# board.net
KiCad netlist of a schematic drawn in EAGLE
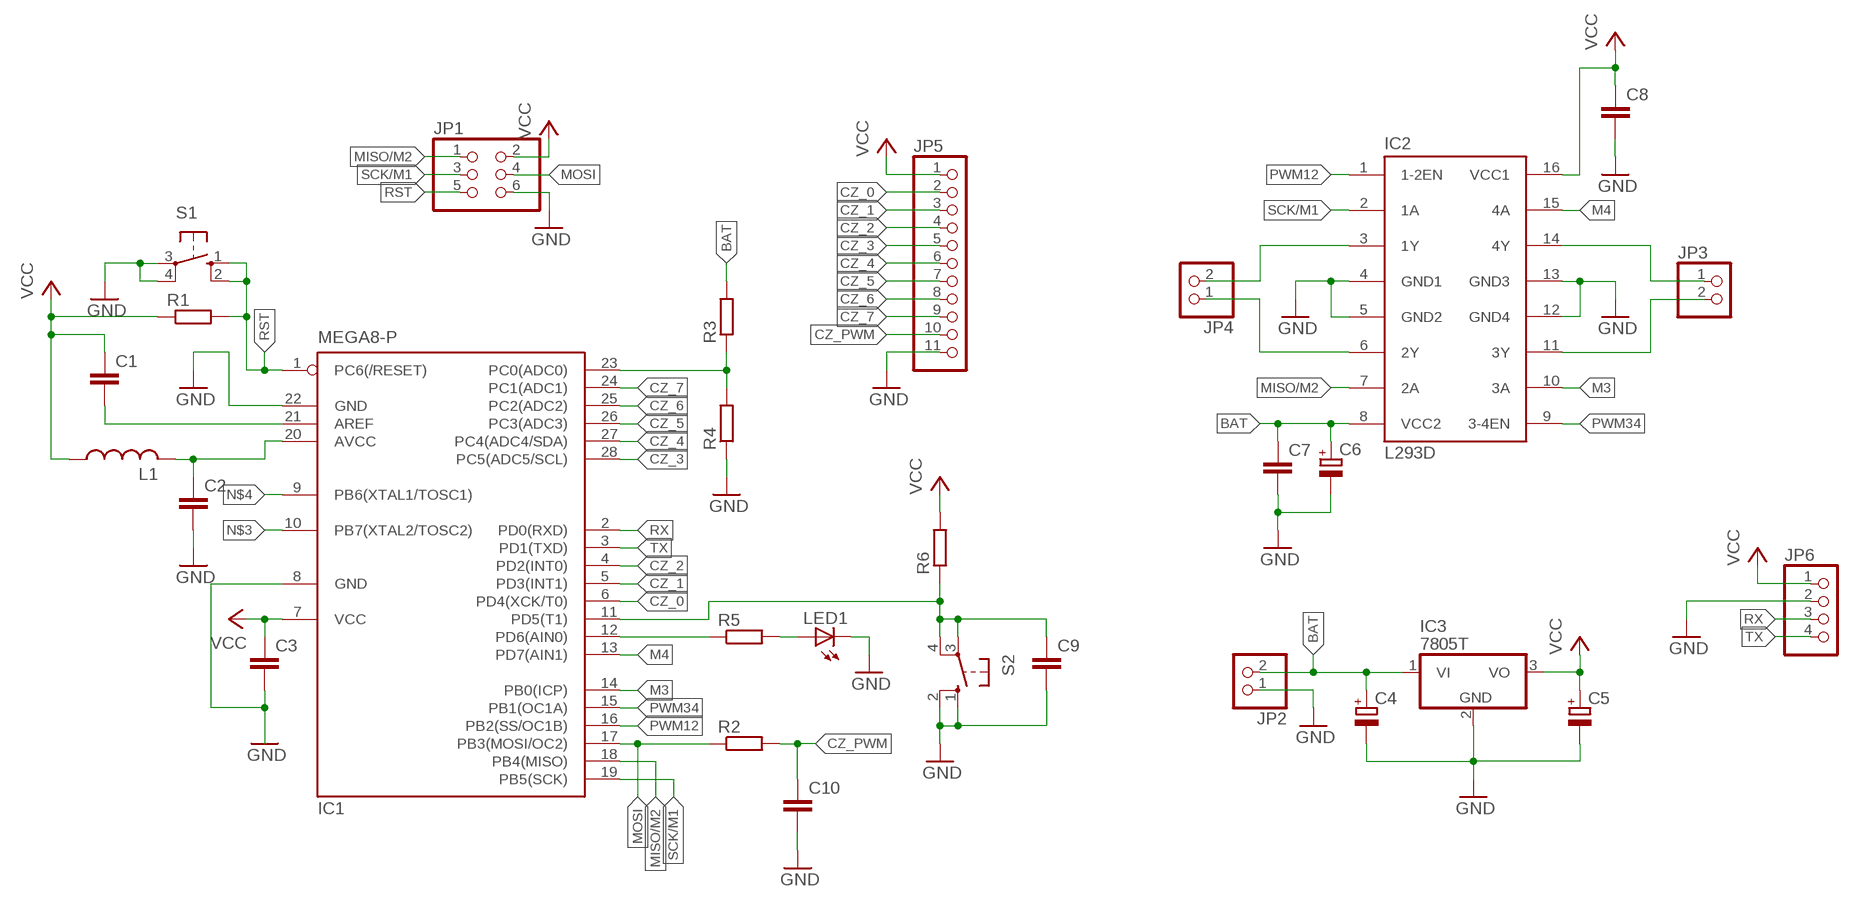
[diagram p0: schematic, sheet 1]

(export (version "E")
  (design (tool "Eeschema 10.0.6"))
  (components
    (comp (ref "C1")
      (value "C-EU025-025X050")
      (footprint "eagle-import:C025-025X050")
      (libsource (lib "eagle-import") (part "C-EU025-025X050"))
    )
    (comp (ref "C2")
      (value "C-EU025-025X050")
      (footprint "eagle-import:C025-025X050")
      (libsource (lib "eagle-import") (part "C-EU025-025X050"))
    )
    (comp (ref "C3")
      (value "C-EU025-025X050")
      (footprint "eagle-import:C025-025X050")
      (libsource (lib "eagle-import") (part "C-EU025-025X050"))
    )
    (comp (ref "C4")
      (value "CPOL-EUE2-5")
      (footprint "eagle-import:E2-5")
      (libsource (lib "eagle-import") (part "CPOL-EUE2-5"))
    )
    (comp (ref "C5")
      (value "CPOL-EUE2-5")
      (footprint "eagle-import:E2-5")
      (libsource (lib "eagle-import") (part "CPOL-EUE2-5"))
    )
    (comp (ref "C6")
      (value "CPOL-EUE2-5")
      (footprint "eagle-import:E2-5")
      (libsource (lib "eagle-import") (part "CPOL-EUE2-5"))
    )
    (comp (ref "C7")
      (value "C-EU025-025X050")
      (footprint "eagle-import:C025-025X050")
      (libsource (lib "eagle-import") (part "C-EU025-025X050"))
    )
    (comp (ref "C8")
      (value "C-EU025-025X050")
      (footprint "eagle-import:C025-025X050")
      (libsource (lib "eagle-import") (part "C-EU025-025X050"))
    )
    (comp (ref "C9")
      (value "C-EU025-025X050")
      (footprint "eagle-import:C025-025X050")
      (libsource (lib "eagle-import") (part "C-EU025-025X050"))
    )
    (comp (ref "C10")
      (value "C-EU050-035X075")
      (footprint "eagle-import:C050-035X075")
      (libsource (lib "eagle-import") (part "C-EU050-035X075"))
    )
    (comp (ref "IC1")
      (value "MEGA8-P")
      (footprint "eagle-import:DIL28-3")
      (libsource (lib "eagle-import") (part "MEGA8-P"))
    )
    (comp (ref "IC2")
      (value "L293D")
      (footprint "eagle-import:DIL16")
      (libsource (lib "eagle-import") (part "L293D"))
    )
    (comp (ref "IC3")
      (value "7805T")
      (footprint "eagle-import:TO220H")
      (libsource (lib "eagle-import") (part "78T05"))
    )
    (comp (ref "JP1")
      (value "PINHD-2X3")
      (footprint "eagle-import:2X03")
      (libsource (lib "eagle-import") (part "PINHD-2X3"))
    )
    (comp (ref "JP2")
      (value "PINHD-1X2")
      (footprint "eagle-import:1X02")
      (libsource (lib "eagle-import") (part "PINHD-1X2"))
    )
    (comp (ref "JP3")
      (value "PINHD-1X2")
      (footprint "eagle-import:1X02")
      (libsource (lib "eagle-import") (part "PINHD-1X2"))
    )
    (comp (ref "JP4")
      (value "PINHD-1X2")
      (footprint "eagle-import:1X02")
      (libsource (lib "eagle-import") (part "PINHD-1X2"))
    )
    (comp (ref "JP5")
      (value "PINHD-1X11")
      (footprint "eagle-import:1X11")
      (libsource (lib "eagle-import") (part "PINHD-1X11"))
    )
    (comp (ref "JP6")
      (value "PINHD-1X4")
      (footprint "eagle-import:1X04")
      (libsource (lib "eagle-import") (part "PINHD-1X4"))
    )
    (comp (ref "L1")
      (value "L-US0204/7")
      (footprint "eagle-import:0204_7")
      (libsource (lib "eagle-import") (part "L-US0204/7"))
    )
    (comp (ref "LED1")
      (value "LED5MM")
      (footprint "eagle-import:LED5MM")
      (libsource (lib "eagle-import") (part "LED5MM"))
    )
    (comp (ref "R1")
      (value "R-EU_0207/7")
      (footprint "eagle-import:0207_7")
      (libsource (lib "eagle-import") (part "R-EU_0207/7"))
    )
    (comp (ref "R2")
      (value "R-EU_0207/7")
      (footprint "eagle-import:0207_7")
      (libsource (lib "eagle-import") (part "R-EU_0207/7"))
    )
    (comp (ref "R3")
      (value "R-EU_0207/7")
      (footprint "eagle-import:0207_7")
      (libsource (lib "eagle-import") (part "R-EU_0207/7"))
    )
    (comp (ref "R4")
      (value "R-EU_0207/7")
      (footprint "eagle-import:0207_7")
      (libsource (lib "eagle-import") (part "R-EU_0207/7"))
    )
    (comp (ref "R5")
      (value "R-EU_0207/7")
      (footprint "eagle-import:0207_7")
      (libsource (lib "eagle-import") (part "R-EU_0207/7"))
    )
    (comp (ref "R6")
      (value "R-EU_0207/7")
      (footprint "eagle-import:0207_7")
      (libsource (lib "eagle-import") (part "R-EU_0207/7"))
    )
    (comp (ref "S1")
      (value "10-XX")
      (footprint "eagle-import:B3F-10XX")
      (fields (field (name "MPN") "B3F-1000"))
      (libsource (lib "eagle-import") (part "10-XX"))
    )
    (comp (ref "S2")
      (value "10-XX")
      (footprint "eagle-import:B3F-10XX")
      (fields (field (name "MPN") "B3F-1000"))
      (libsource (lib "eagle-import") (part "10-XX"))
    )
  )
  (nets
    (net (code "1") (name "BAT") (class "Default")
      (node (ref "C4") (pin "+") (pinfunction "+_+") (pintype "passive"))
      (node (ref "C6") (pin "+") (pinfunction "+_+") (pintype "passive"))
      (node (ref "C7") (pin "1") (pinfunction "1_1") (pintype "passive"))
      (node (ref "IC2") (pin "8") (pinfunction "VCC2_8") (pintype "power_in"))
      (node (ref "IC3") (pin "1") (pinfunction "VI_1") (pintype "input"))
      (node (ref "JP2") (pin "2") (pinfunction "2_2") (pintype "passive"))
      (node (ref "R3") (pin "2") (pinfunction "2_2") (pintype "passive"))
    )
    (net (code "2") (name "CZ_0") (class "Default")
      (node (ref "IC1") (pin "6") (pinfunction "PD4(XCK/T0)_6") (pintype "bidirectional"))
      (node (ref "JP5") (pin "2") (pinfunction "2_2") (pintype "passive"))
    )
    (net (code "3") (name "CZ_1") (class "Default")
      (node (ref "IC1") (pin "5") (pinfunction "PD3(INT1)_5") (pintype "bidirectional"))
      (node (ref "JP5") (pin "3") (pinfunction "3_3") (pintype "passive"))
    )
    (net (code "4") (name "CZ_2") (class "Default")
      (node (ref "IC1") (pin "4") (pinfunction "PD2(INT0)_4") (pintype "bidirectional"))
      (node (ref "JP5") (pin "4") (pinfunction "4_4") (pintype "passive"))
    )
    (net (code "5") (name "CZ_3") (class "Default")
      (node (ref "IC1") (pin "28") (pinfunction "PC5(ADC5/SCL)_28") (pintype "bidirectional"))
      (node (ref "JP5") (pin "5") (pinfunction "5_5") (pintype "passive"))
    )
    (net (code "6") (name "CZ_4") (class "Default")
      (node (ref "IC1") (pin "27") (pinfunction "PC4(ADC4/SDA)_27") (pintype "bidirectional"))
      (node (ref "JP5") (pin "6") (pinfunction "6_6") (pintype "passive"))
    )
    (net (code "7") (name "CZ_5") (class "Default")
      (node (ref "IC1") (pin "26") (pinfunction "PC3(ADC3)_26") (pintype "bidirectional"))
      (node (ref "JP5") (pin "7") (pinfunction "7_7") (pintype "passive"))
    )
    (net (code "8") (name "CZ_6") (class "Default")
      (node (ref "IC1") (pin "25") (pinfunction "PC2(ADC2)_25") (pintype "bidirectional"))
      (node (ref "JP5") (pin "8") (pinfunction "8_8") (pintype "passive"))
    )
    (net (code "9") (name "CZ_7") (class "Default")
      (node (ref "IC1") (pin "24") (pinfunction "PC1(ADC1)_24") (pintype "bidirectional"))
      (node (ref "JP5") (pin "9") (pinfunction "9_9") (pintype "passive"))
    )
    (net (code "10") (name "CZ_PWM") (class "Default")
      (node (ref "C10") (pin "1") (pinfunction "1_1") (pintype "passive"))
      (node (ref "JP5") (pin "10") (pinfunction "10_10") (pintype "passive"))
      (node (ref "R2") (pin "2") (pinfunction "2_2") (pintype "passive"))
    )
    (net (code "11") (name "GND") (class "Default")
      (node (ref "C10") (pin "2") (pinfunction "2_2") (pintype "passive"))
      (node (ref "C2") (pin "2") (pinfunction "2_2") (pintype "passive"))
      (node (ref "C3") (pin "2") (pinfunction "2_2") (pintype "passive"))
      (node (ref "C4") (pin "-") (pinfunction "-_-") (pintype "passive"))
      (node (ref "C5") (pin "-") (pinfunction "-_-") (pintype "passive"))
      (node (ref "C6") (pin "-") (pinfunction "-_-") (pintype "passive"))
      (node (ref "C7") (pin "2") (pinfunction "2_2") (pintype "passive"))
      (node (ref "C8") (pin "2") (pinfunction "2_2") (pintype "passive"))
      (node (ref "C9") (pin "2") (pinfunction "2_2") (pintype "passive"))
      (node (ref "IC1") (pin "22") (pinfunction "GND_22") (pintype "power_in"))
      (node (ref "IC1") (pin "8") (pinfunction "GND_8") (pintype "power_in"))
      (node (ref "IC2") (pin "12") (pinfunction "GND4_12") (pintype "power_in"))
      (node (ref "IC2") (pin "13") (pinfunction "GND3_13") (pintype "power_in"))
      (node (ref "IC2") (pin "4") (pinfunction "GND1_4") (pintype "power_in"))
      (node (ref "IC2") (pin "5") (pinfunction "GND2_5") (pintype "power_in"))
      (node (ref "IC3") (pin "2") (pinfunction "GND_2") (pintype "passive"))
      (node (ref "JP1") (pin "6") (pinfunction "6_6") (pintype "passive"))
      (node (ref "JP2") (pin "1") (pinfunction "1_1") (pintype "passive"))
      (node (ref "JP5") (pin "11") (pinfunction "11_11") (pintype "passive"))
      (node (ref "JP6") (pin "2") (pinfunction "2_2") (pintype "passive"))
      (node (ref "LED1") (pin "K") (pinfunction "C_K") (pintype "passive"))
      (node (ref "R4") (pin "1") (pinfunction "1_1") (pintype "passive"))
      (node (ref "S1") (pin "3") (pinfunction "P_3") (pintype "passive"))
      (node (ref "S1") (pin "4") (pinfunction "P1_4") (pintype "passive"))
      (node (ref "S2") (pin "1") (pinfunction "S_1") (pintype "passive"))
      (node (ref "S2") (pin "2") (pinfunction "S1_2") (pintype "passive"))
    )
    (net (code "12") (name "M3") (class "Default")
      (node (ref "IC1") (pin "14") (pinfunction "PB0(ICP)_14") (pintype "bidirectional"))
      (node (ref "IC2") (pin "10") (pinfunction "3A_10") (pintype "input"))
    )
    (net (code "13") (name "M4") (class "Default")
      (node (ref "IC1") (pin "13") (pinfunction "PD7(AIN1)_13") (pintype "bidirectional"))
      (node (ref "IC2") (pin "15") (pinfunction "4A_15") (pintype "input"))
    )
    (net (code "14") (name "MISO{slash}M2") (class "Default")
      (node (ref "IC1") (pin "18") (pinfunction "PB4(MISO)_18") (pintype "bidirectional"))
      (node (ref "IC2") (pin "7") (pinfunction "2A_7") (pintype "input"))
      (node (ref "JP1") (pin "1") (pinfunction "1_1") (pintype "passive"))
    )
    (net (code "15") (name "MOSI") (class "Default")
      (node (ref "IC1") (pin "17") (pinfunction "PB3(MOSI/OC2)_17") (pintype "bidirectional"))
      (node (ref "JP1") (pin "4") (pinfunction "4_4") (pintype "passive"))
      (node (ref "R2") (pin "1") (pinfunction "1_1") (pintype "passive"))
    )
    (net (code "16") (name "N$3") (class "Default")
      (node (ref "IC1") (pin "10") (pinfunction "PB7(XTAL2/TOSC2)_10") (pintype "bidirectional"))
    )
    (net (code "17") (name "N$4") (class "Default")
      (node (ref "IC1") (pin "9") (pinfunction "PB6(XTAL1/TOSC1)_9") (pintype "bidirectional"))
    )
    (net (code "18") (name "Net-(IC1-AREF)") (class "Default")
      (node (ref "C1") (pin "2") (pinfunction "2_2") (pintype "passive"))
      (node (ref "IC1") (pin "21") (pinfunction "AREF_21") (pintype "passive"))
    )
    (net (code "19") (name "Net-(IC1-AVCC)") (class "Default")
      (node (ref "C2") (pin "1") (pinfunction "1_1") (pintype "passive"))
      (node (ref "IC1") (pin "20") (pinfunction "AVCC_20") (pintype "power_in"))
      (node (ref "L1") (pin "2") (pinfunction "2_2") (pintype "passive"))
    )
    (net (code "20") (name "Net-(IC1-PC0(ADC0))") (class "Default")
      (node (ref "IC1") (pin "23") (pinfunction "PC0(ADC0)_23") (pintype "bidirectional"))
      (node (ref "R3") (pin "1") (pinfunction "1_1") (pintype "passive"))
      (node (ref "R4") (pin "2") (pinfunction "2_2") (pintype "passive"))
    )
    (net (code "21") (name "Net-(IC1-PD5(T1))") (class "Default")
      (node (ref "C9") (pin "1") (pinfunction "1_1") (pintype "passive"))
      (node (ref "IC1") (pin "11") (pinfunction "PD5(T1)_11") (pintype "bidirectional"))
      (node (ref "R6") (pin "1") (pinfunction "1_1") (pintype "passive"))
      (node (ref "S2") (pin "3") (pinfunction "P_3") (pintype "passive"))
      (node (ref "S2") (pin "4") (pinfunction "P1_4") (pintype "passive"))
    )
    (net (code "22") (name "Net-(IC1-PD6(AIN0))") (class "Default")
      (node (ref "IC1") (pin "12") (pinfunction "PD6(AIN0)_12") (pintype "bidirectional"))
      (node (ref "R5") (pin "1") (pinfunction "1_1") (pintype "passive"))
    )
    (net (code "23") (name "Net-(IC2-1Y)") (class "Default")
      (node (ref "IC2") (pin "3") (pinfunction "1Y_3") (pintype "output"))
      (node (ref "JP4") (pin "2") (pinfunction "2_2") (pintype "passive"))
    )
    (net (code "24") (name "Net-(IC2-2Y)") (class "Default")
      (node (ref "IC2") (pin "6") (pinfunction "2Y_6") (pintype "output"))
      (node (ref "JP4") (pin "1") (pinfunction "1_1") (pintype "passive"))
    )
    (net (code "25") (name "Net-(IC2-3Y)") (class "Default")
      (node (ref "IC2") (pin "11") (pinfunction "3Y_11") (pintype "output"))
      (node (ref "JP3") (pin "2") (pinfunction "2_2") (pintype "passive"))
    )
    (net (code "26") (name "Net-(IC2-4Y)") (class "Default")
      (node (ref "IC2") (pin "14") (pinfunction "4Y_14") (pintype "output"))
      (node (ref "JP3") (pin "1") (pinfunction "1_1") (pintype "passive"))
    )
    (net (code "27") (name "Net-(LED1-PadA)") (class "Default")
      (node (ref "LED1") (pin "A") (pinfunction "A_A") (pintype "passive"))
      (node (ref "R5") (pin "2") (pinfunction "2_2") (pintype "passive"))
    )
    (net (code "28") (name "PWM12") (class "Default")
      (node (ref "IC1") (pin "16") (pinfunction "PB2(SS/OC1B)_16") (pintype "bidirectional"))
      (node (ref "IC2") (pin "1") (pinfunction "1-2EN_1") (pintype "input"))
    )
    (net (code "29") (name "PWM34") (class "Default")
      (node (ref "IC1") (pin "15") (pinfunction "PB1(OC1A)_15") (pintype "bidirectional"))
      (node (ref "IC2") (pin "9") (pinfunction "3-4EN_9") (pintype "input"))
    )
    (net (code "30") (name "RST") (class "Default")
      (node (ref "IC1") (pin "1") (pinfunction "PC6(/RESET)_1") (pintype "bidirectional"))
      (node (ref "JP1") (pin "5") (pinfunction "5_5") (pintype "passive"))
      (node (ref "R1") (pin "2") (pinfunction "2_2") (pintype "passive"))
      (node (ref "S1") (pin "1") (pinfunction "S_1") (pintype "passive"))
      (node (ref "S1") (pin "2") (pinfunction "S1_2") (pintype "passive"))
    )
    (net (code "31") (name "RX") (class "Default")
      (node (ref "IC1") (pin "2") (pinfunction "PD0(RXD)_2") (pintype "bidirectional"))
      (node (ref "JP6") (pin "3") (pinfunction "3_3") (pintype "passive"))
    )
    (net (code "32") (name "SCK{slash}M1") (class "Default")
      (node (ref "IC1") (pin "19") (pinfunction "PB5(SCK)_19") (pintype "bidirectional"))
      (node (ref "IC2") (pin "2") (pinfunction "1A_2") (pintype "input"))
      (node (ref "JP1") (pin "3") (pinfunction "3_3") (pintype "passive"))
    )
    (net (code "33") (name "TX") (class "Default")
      (node (ref "IC1") (pin "3") (pinfunction "PD1(TXD)_3") (pintype "bidirectional"))
      (node (ref "JP6") (pin "4") (pinfunction "4_4") (pintype "passive"))
    )
    (net (code "34") (name "VCC") (class "Default")
      (node (ref "C1") (pin "1") (pinfunction "1_1") (pintype "passive"))
      (node (ref "C3") (pin "1") (pinfunction "1_1") (pintype "passive"))
      (node (ref "C5") (pin "+") (pinfunction "+_+") (pintype "passive"))
      (node (ref "C8") (pin "1") (pinfunction "1_1") (pintype "passive"))
      (node (ref "IC1") (pin "7") (pinfunction "VCC_7") (pintype "power_in"))
      (node (ref "IC2") (pin "16") (pinfunction "VCC1_16") (pintype "power_in"))
      (node (ref "IC3") (pin "3") (pinfunction "VO_3") (pintype "passive"))
      (node (ref "JP1") (pin "2") (pinfunction "2_2") (pintype "passive"))
      (node (ref "JP5") (pin "1") (pinfunction "1_1") (pintype "passive"))
      (node (ref "JP6") (pin "1") (pinfunction "1_1") (pintype "passive"))
      (node (ref "L1") (pin "1") (pinfunction "1_1") (pintype "passive"))
      (node (ref "R1") (pin "1") (pinfunction "1_1") (pintype "passive"))
      (node (ref "R6") (pin "2") (pinfunction "2_2") (pintype "passive"))
    )
  )
)
